# CPU_CORE_POWER_GND.net
KiCad netlist of a schematic drawn in Altium Designer
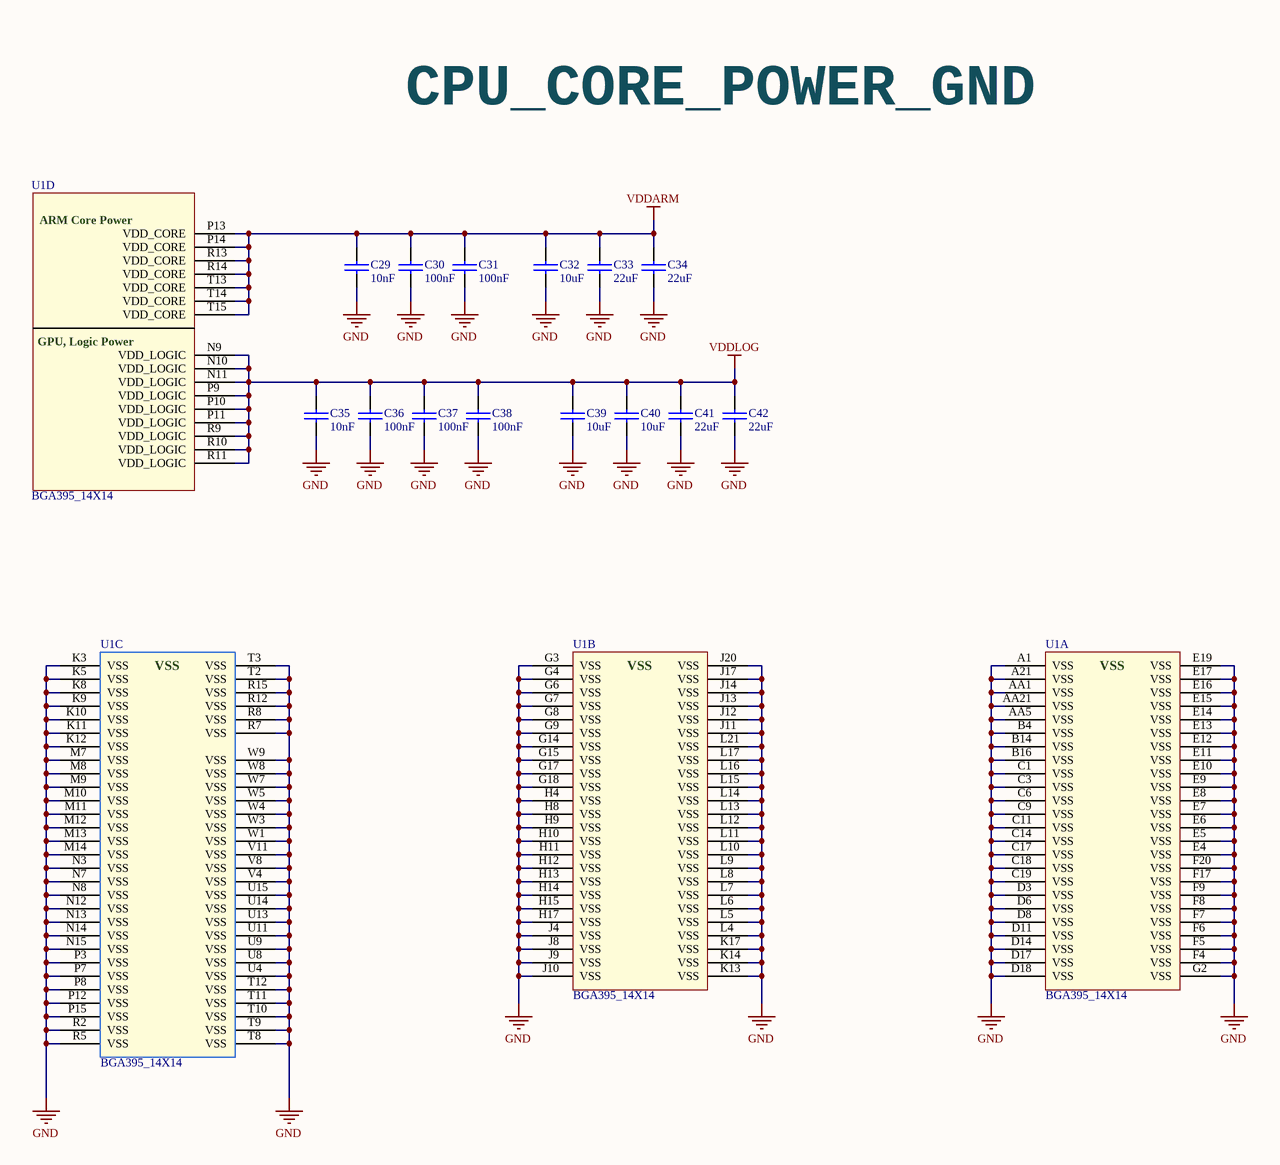
[diagram p0: CPU_CORE_POWER_GND.SchDoc]

(export (version "E")
  (design (tool "Eeschema 10.0.6"))
  (components
    (comp (ref "C29")
      (value "10nF")
      (footprint "0402_CC - C")
      (libsource (lib "AAR_RockChip_RK3328") (part "CAP_NP"))
    )
    (comp (ref "C30")
      (value "100nF")
      (footprint "0402_CC - C")
      (libsource (lib "AAR_RockChip_RK3328") (part "CAP_NP"))
    )
    (comp (ref "C31")
      (value "100nF")
      (footprint "0402_CC - C")
      (libsource (lib "AAR_RockChip_RK3328") (part "CAP_NP"))
    )
    (comp (ref "C32")
      (value "10uF")
      (footprint "0603_CC")
      (libsource (lib "AAR_RockChip_RK3328") (part "CAP_NP"))
    )
    (comp (ref "C33")
      (value "22uF")
      (footprint "0603_CC")
      (libsource (lib "AAR_RockChip_RK3328") (part "CAP_NP"))
    )
    (comp (ref "C34")
      (value "22uF")
      (footprint "0603_CC")
      (libsource (lib "AAR_RockChip_RK3328") (part "CAP_NP"))
    )
    (comp (ref "C35")
      (value "10nF")
      (footprint "0402_CC - C")
      (libsource (lib "AAR_RockChip_RK3328") (part "CAP_NP"))
    )
    (comp (ref "C36")
      (value "100nF")
      (footprint "0402_CC - C")
      (libsource (lib "AAR_RockChip_RK3328") (part "CAP_NP"))
    )
    (comp (ref "C37")
      (value "100nF")
      (footprint "0402_CC - C")
      (libsource (lib "AAR_RockChip_RK3328") (part "CAP_NP"))
    )
    (comp (ref "C38")
      (value "100nF")
      (footprint "0402_CC - C")
      (libsource (lib "AAR_RockChip_RK3328") (part "CAP_NP"))
    )
    (comp (ref "C39")
      (value "10uF")
      (footprint "0603_CC")
      (libsource (lib "AAR_RockChip_RK3328") (part "CAP_NP"))
    )
    (comp (ref "C40")
      (value "10uF")
      (footprint "0603_CC")
      (libsource (lib "AAR_RockChip_RK3328") (part "CAP_NP"))
    )
    (comp (ref "C41")
      (value "22uF")
      (footprint "0603_CC")
      (libsource (lib "AAR_RockChip_RK3328") (part "CAP_NP"))
    )
    (comp (ref "C42")
      (value "22uF")
      (footprint "0603_CC")
      (libsource (lib "AAR_RockChip_RK3328") (part "CAP_NP"))
    )
    (comp (ref "U1")
      (value "BGA395_14X14")
      (footprint "BGA395C65P21X21_1750X1750X117")
      (description "By AAR")
      (libsource (lib "AAR_RockChip_RK3328") (part "RK3328"))
    )
  )
  (nets
    (net (code "1") (name "GND") (class "Default")
      (node (ref "C29") (pin "2") (pinfunction "2_2") (pintype "passive"))
      (node (ref "C30") (pin "2") (pinfunction "2_2") (pintype "passive"))
      (node (ref "C31") (pin "2") (pinfunction "2_2") (pintype "passive"))
      (node (ref "C32") (pin "2") (pinfunction "2_2") (pintype "passive"))
      (node (ref "C33") (pin "2") (pinfunction "2_2") (pintype "passive"))
      (node (ref "C34") (pin "2") (pinfunction "2_2") (pintype "passive"))
      (node (ref "C35") (pin "2") (pinfunction "2_2") (pintype "passive"))
      (node (ref "C36") (pin "2") (pinfunction "2_2") (pintype "passive"))
      (node (ref "C37") (pin "2") (pinfunction "2_2") (pintype "passive"))
      (node (ref "C38") (pin "2") (pinfunction "2_2") (pintype "passive"))
      (node (ref "C39") (pin "2") (pinfunction "2_2") (pintype "passive"))
      (node (ref "C40") (pin "2") (pinfunction "2_2") (pintype "passive"))
      (node (ref "C41") (pin "2") (pinfunction "2_2") (pintype "passive"))
      (node (ref "C42") (pin "2") (pinfunction "2_2") (pintype "passive"))
      (node (ref "U1") (pin "A1") (pinfunction "VSS_A1") (pintype "power_in"))
      (node (ref "U1") (pin "A21") (pinfunction "VSS_A21") (pintype "power_in"))
      (node (ref "U1") (pin "AA1") (pinfunction "VSS_AA1") (pintype "power_in"))
      (node (ref "U1") (pin "AA21") (pinfunction "VSS_AA21") (pintype "power_in"))
      (node (ref "U1") (pin "AA5") (pinfunction "VSS_AA5") (pintype "power_in"))
      (node (ref "U1") (pin "B14") (pinfunction "VSS_B14") (pintype "power_in"))
      (node (ref "U1") (pin "B16") (pinfunction "VSS_B16") (pintype "power_in"))
      (node (ref "U1") (pin "B4") (pinfunction "VSS_B4") (pintype "power_in"))
      (node (ref "U1") (pin "C1") (pinfunction "VSS_C1") (pintype "power_in"))
      (node (ref "U1") (pin "C11") (pinfunction "VSS_C11") (pintype "power_in"))
      (node (ref "U1") (pin "C14") (pinfunction "VSS_C14") (pintype "power_in"))
      (node (ref "U1") (pin "C17") (pinfunction "VSS_C17") (pintype "power_in"))
      (node (ref "U1") (pin "C18") (pinfunction "VSS_C18") (pintype "power_in"))
      (node (ref "U1") (pin "C19") (pinfunction "VSS_C19") (pintype "power_in"))
      (node (ref "U1") (pin "C3") (pinfunction "VSS_C3") (pintype "power_in"))
      (node (ref "U1") (pin "C6") (pinfunction "VSS_C6") (pintype "power_in"))
      (node (ref "U1") (pin "C9") (pinfunction "VSS_C9") (pintype "power_in"))
      (node (ref "U1") (pin "D11") (pinfunction "VSS_D11") (pintype "power_in"))
      (node (ref "U1") (pin "D14") (pinfunction "VSS_D14") (pintype "power_in"))
      (node (ref "U1") (pin "D17") (pinfunction "VSS_D17") (pintype "power_in"))
      (node (ref "U1") (pin "D18") (pinfunction "VSS_D18") (pintype "power_in"))
      (node (ref "U1") (pin "D3") (pinfunction "VSS_D3") (pintype "power_in"))
      (node (ref "U1") (pin "D6") (pinfunction "VSS_D6") (pintype "power_in"))
      (node (ref "U1") (pin "D8") (pinfunction "VSS_D8") (pintype "power_in"))
      (node (ref "U1") (pin "E10") (pinfunction "VSS_E10") (pintype "power_in"))
      (node (ref "U1") (pin "E11") (pinfunction "VSS_E11") (pintype "power_in"))
      (node (ref "U1") (pin "E12") (pinfunction "VSS_E12") (pintype "power_in"))
      (node (ref "U1") (pin "E13") (pinfunction "VSS_E13") (pintype "power_in"))
      (node (ref "U1") (pin "E14") (pinfunction "VSS_E14") (pintype "power_in"))
      (node (ref "U1") (pin "E15") (pinfunction "VSS_E15") (pintype "power_in"))
      (node (ref "U1") (pin "E16") (pinfunction "VSS_E16") (pintype "power_in"))
      (node (ref "U1") (pin "E17") (pinfunction "VSS_E17") (pintype "power_in"))
      (node (ref "U1") (pin "E19") (pinfunction "VSS_E19") (pintype "power_in"))
      (node (ref "U1") (pin "E4") (pinfunction "VSS_E4") (pintype "power_in"))
      (node (ref "U1") (pin "E5") (pinfunction "VSS_E5") (pintype "power_in"))
      (node (ref "U1") (pin "E6") (pinfunction "VSS_E6") (pintype "power_in"))
      (node (ref "U1") (pin "E7") (pinfunction "VSS_E7") (pintype "power_in"))
      (node (ref "U1") (pin "E8") (pinfunction "VSS_E8") (pintype "power_in"))
      (node (ref "U1") (pin "E9") (pinfunction "VSS_E9") (pintype "power_in"))
      (node (ref "U1") (pin "F17") (pinfunction "VSS_F17") (pintype "power_in"))
      (node (ref "U1") (pin "F20") (pinfunction "VSS_F20") (pintype "power_in"))
      (node (ref "U1") (pin "F4") (pinfunction "VSS_F4") (pintype "power_in"))
      (node (ref "U1") (pin "F5") (pinfunction "VSS_F5") (pintype "power_in"))
      (node (ref "U1") (pin "F6") (pinfunction "VSS_F6") (pintype "power_in"))
      (node (ref "U1") (pin "F7") (pinfunction "VSS_F7") (pintype "power_in"))
      (node (ref "U1") (pin "F8") (pinfunction "VSS_F8") (pintype "power_in"))
      (node (ref "U1") (pin "F9") (pinfunction "VSS_F9") (pintype "power_in"))
      (node (ref "U1") (pin "G14") (pinfunction "VSS_G14") (pintype "power_in"))
      (node (ref "U1") (pin "G15") (pinfunction "VSS_G15") (pintype "power_in"))
      (node (ref "U1") (pin "G17") (pinfunction "VSS_G17") (pintype "power_in"))
      (node (ref "U1") (pin "G18") (pinfunction "VSS_G18") (pintype "power_in"))
      (node (ref "U1") (pin "G2") (pinfunction "VSS_G2") (pintype "power_in"))
      (node (ref "U1") (pin "G3") (pinfunction "VSS_G3") (pintype "power_in"))
      (node (ref "U1") (pin "G4") (pinfunction "VSS_G4") (pintype "power_in"))
      (node (ref "U1") (pin "G6") (pinfunction "VSS_G6") (pintype "power_in"))
      (node (ref "U1") (pin "G7") (pinfunction "VSS_G7") (pintype "power_in"))
      (node (ref "U1") (pin "G8") (pinfunction "VSS_G8") (pintype "power_in"))
      (node (ref "U1") (pin "G9") (pinfunction "VSS_G9") (pintype "power_in"))
      (node (ref "U1") (pin "H10") (pinfunction "VSS_H10") (pintype "power_in"))
      (node (ref "U1") (pin "H11") (pinfunction "VSS_H11") (pintype "power_in"))
      (node (ref "U1") (pin "H12") (pinfunction "VSS_H12") (pintype "power_in"))
      (node (ref "U1") (pin "H13") (pinfunction "VSS_H13") (pintype "power_in"))
      (node (ref "U1") (pin "H14") (pinfunction "VSS_H14") (pintype "power_in"))
      (node (ref "U1") (pin "H15") (pinfunction "VSS_H15") (pintype "power_in"))
      (node (ref "U1") (pin "H17") (pinfunction "VSS_H17") (pintype "power_in"))
      (node (ref "U1") (pin "H4") (pinfunction "VSS_H4") (pintype "power_in"))
      (node (ref "U1") (pin "H8") (pinfunction "VSS_H8") (pintype "power_in"))
      (node (ref "U1") (pin "H9") (pinfunction "VSS_H9") (pintype "power_in"))
      (node (ref "U1") (pin "J10") (pinfunction "VSS_J10") (pintype "power_in"))
      (node (ref "U1") (pin "J11") (pinfunction "VSS_J11") (pintype "power_in"))
      (node (ref "U1") (pin "J12") (pinfunction "VSS_J12") (pintype "power_in"))
      (node (ref "U1") (pin "J13") (pinfunction "VSS_J13") (pintype "power_in"))
      (node (ref "U1") (pin "J14") (pinfunction "VSS_J14") (pintype "power_in"))
      (node (ref "U1") (pin "J17") (pinfunction "VSS_J17") (pintype "power_in"))
      (node (ref "U1") (pin "J20") (pinfunction "VSS_J20") (pintype "power_in"))
      (node (ref "U1") (pin "J4") (pinfunction "VSS_J4") (pintype "power_in"))
      (node (ref "U1") (pin "J8") (pinfunction "VSS_J8") (pintype "power_in"))
      (node (ref "U1") (pin "J9") (pinfunction "VSS_J9") (pintype "power_in"))
      (node (ref "U1") (pin "K10") (pinfunction "VSS_K10") (pintype "power_in"))
      (node (ref "U1") (pin "K11") (pinfunction "VSS_K11") (pintype "power_in"))
      (node (ref "U1") (pin "K12") (pinfunction "VSS_K12") (pintype "power_in"))
      (node (ref "U1") (pin "K13") (pinfunction "VSS_K13") (pintype "power_in"))
      (node (ref "U1") (pin "K14") (pinfunction "VSS_K14") (pintype "power_in"))
      (node (ref "U1") (pin "K17") (pinfunction "VSS_K17") (pintype "power_in"))
      (node (ref "U1") (pin "K3") (pinfunction "VSS_K3") (pintype "power_in"))
      (node (ref "U1") (pin "K5") (pinfunction "VSS_K5") (pintype "power_in"))
      (node (ref "U1") (pin "K8") (pinfunction "VSS_K8") (pintype "power_in"))
      (node (ref "U1") (pin "K9") (pinfunction "VSS_K9") (pintype "power_in"))
      (node (ref "U1") (pin "L10") (pinfunction "VSS_L10") (pintype "power_in"))
      (node (ref "U1") (pin "L11") (pinfunction "VSS_L11") (pintype "power_in"))
      (node (ref "U1") (pin "L12") (pinfunction "VSS_L12") (pintype "power_in"))
      (node (ref "U1") (pin "L13") (pinfunction "VSS_L13") (pintype "power_in"))
      (node (ref "U1") (pin "L14") (pinfunction "VSS_L14") (pintype "power_in"))
      (node (ref "U1") (pin "L15") (pinfunction "VSS_L15") (pintype "power_in"))
      (node (ref "U1") (pin "L16") (pinfunction "VSS_L16") (pintype "power_in"))
      (node (ref "U1") (pin "L17") (pinfunction "VSS_L17") (pintype "power_in"))
      (node (ref "U1") (pin "L21") (pinfunction "VSS_L21") (pintype "power_in"))
      (node (ref "U1") (pin "L4") (pinfunction "VSS_L4") (pintype "power_in"))
      (node (ref "U1") (pin "L5") (pinfunction "VSS_L5") (pintype "power_in"))
      (node (ref "U1") (pin "L6") (pinfunction "VSS_L6") (pintype "power_in"))
      (node (ref "U1") (pin "L7") (pinfunction "VSS_L7") (pintype "power_in"))
      (node (ref "U1") (pin "L8") (pinfunction "VSS_L8") (pintype "power_in"))
      (node (ref "U1") (pin "L9") (pinfunction "VSS_L9") (pintype "power_in"))
      (node (ref "U1") (pin "M10") (pinfunction "VSS_M10") (pintype "power_in"))
      (node (ref "U1") (pin "M11") (pinfunction "VSS_M11") (pintype "power_in"))
      (node (ref "U1") (pin "M12") (pinfunction "VSS_M12") (pintype "power_in"))
      (node (ref "U1") (pin "M13") (pinfunction "VSS_M13") (pintype "power_in"))
      (node (ref "U1") (pin "M14") (pinfunction "VSS_M14") (pintype "power_in"))
      (node (ref "U1") (pin "M7") (pinfunction "VSS_M7") (pintype "power_in"))
      (node (ref "U1") (pin "M8") (pinfunction "VSS_M8") (pintype "power_in"))
      (node (ref "U1") (pin "M9") (pinfunction "VSS_M9") (pintype "power_in"))
      (node (ref "U1") (pin "N12") (pinfunction "VSS_N12") (pintype "power_in"))
      (node (ref "U1") (pin "N13") (pinfunction "VSS_N13") (pintype "power_in"))
      (node (ref "U1") (pin "N14") (pinfunction "VSS_N14") (pintype "power_in"))
      (node (ref "U1") (pin "N15") (pinfunction "VSS_N15") (pintype "power_in"))
      (node (ref "U1") (pin "N3") (pinfunction "VSS_N3") (pintype "power_in"))
      (node (ref "U1") (pin "N7") (pinfunction "VSS_N7") (pintype "power_in"))
      (node (ref "U1") (pin "N8") (pinfunction "VSS_N8") (pintype "power_in"))
      (node (ref "U1") (pin "P12") (pinfunction "VSS_P12") (pintype "power_in"))
      (node (ref "U1") (pin "P15") (pinfunction "VSS_P15") (pintype "power_in"))
      (node (ref "U1") (pin "P3") (pinfunction "VSS_P3") (pintype "power_in"))
      (node (ref "U1") (pin "P7") (pinfunction "VSS_P7") (pintype "power_in"))
      (node (ref "U1") (pin "P8") (pinfunction "VSS_P8") (pintype "power_in"))
      (node (ref "U1") (pin "R12") (pinfunction "VSS_R12") (pintype "power_in"))
      (node (ref "U1") (pin "R15") (pinfunction "VSS_R15") (pintype "power_in"))
      (node (ref "U1") (pin "R2") (pinfunction "VSS_R2") (pintype "power_in"))
      (node (ref "U1") (pin "R5") (pinfunction "VSS_R5") (pintype "power_in"))
      (node (ref "U1") (pin "R7") (pinfunction "VSS_R7") (pintype "power_in"))
      (node (ref "U1") (pin "R8") (pinfunction "VSS_R8") (pintype "power_in"))
      (node (ref "U1") (pin "T10") (pinfunction "VSS_T10") (pintype "power_in"))
      (node (ref "U1") (pin "T11") (pinfunction "VSS_T11") (pintype "power_in"))
      (node (ref "U1") (pin "T12") (pinfunction "VSS_T12") (pintype "power_in"))
      (node (ref "U1") (pin "T2") (pinfunction "VSS_T2") (pintype "power_in"))
      (node (ref "U1") (pin "T3") (pinfunction "VSS_T3") (pintype "power_in"))
      (node (ref "U1") (pin "T8") (pinfunction "VSS_T8") (pintype "power_in"))
      (node (ref "U1") (pin "T9") (pinfunction "VSS_T9") (pintype "power_in"))
      (node (ref "U1") (pin "U11") (pinfunction "VSS_U11") (pintype "power_in"))
      (node (ref "U1") (pin "U13") (pinfunction "VSS_U13") (pintype "power_in"))
      (node (ref "U1") (pin "U14") (pinfunction "VSS_U14") (pintype "power_in"))
      (node (ref "U1") (pin "U15") (pinfunction "VSS_U15") (pintype "power_in"))
      (node (ref "U1") (pin "U4") (pinfunction "VSS_U4") (pintype "power_in"))
      (node (ref "U1") (pin "U8") (pinfunction "VSS_U8") (pintype "power_in"))
      (node (ref "U1") (pin "U9") (pinfunction "VSS_U9") (pintype "power_in"))
      (node (ref "U1") (pin "V11") (pinfunction "VSS_V11") (pintype "power_in"))
      (node (ref "U1") (pin "V4") (pinfunction "VSS_V4") (pintype "power_in"))
      (node (ref "U1") (pin "V8") (pinfunction "VSS_V8") (pintype "power_in"))
      (node (ref "U1") (pin "W1") (pinfunction "VSS_W1") (pintype "power_in"))
      (node (ref "U1") (pin "W3") (pinfunction "VSS_W3") (pintype "power_in"))
      (node (ref "U1") (pin "W4") (pinfunction "VSS_W4") (pintype "power_in"))
      (node (ref "U1") (pin "W5") (pinfunction "VSS_W5") (pintype "power_in"))
      (node (ref "U1") (pin "W7") (pinfunction "VSS_W7") (pintype "power_in"))
      (node (ref "U1") (pin "W8") (pinfunction "VSS_W8") (pintype "power_in"))
      (node (ref "U1") (pin "W9") (pinfunction "VSS_W9") (pintype "power_in"))
    )
    (net (code "2") (name "VDDARM") (class "Default")
      (node (ref "C29") (pin "1") (pinfunction "1_1") (pintype "passive"))
      (node (ref "C30") (pin "1") (pinfunction "1_1") (pintype "passive"))
      (node (ref "C31") (pin "1") (pinfunction "1_1") (pintype "passive"))
      (node (ref "C32") (pin "1") (pinfunction "1_1") (pintype "passive"))
      (node (ref "C33") (pin "1") (pinfunction "1_1") (pintype "passive"))
      (node (ref "C34") (pin "1") (pinfunction "1_1") (pintype "passive"))
      (node (ref "U1") (pin "P13") (pinfunction "VDD_CORE_P13") (pintype "power_in"))
      (node (ref "U1") (pin "P14") (pinfunction "VDD_CORE_P14") (pintype "power_in"))
      (node (ref "U1") (pin "R13") (pinfunction "VDD_CORE_R13") (pintype "power_in"))
      (node (ref "U1") (pin "R14") (pinfunction "VDD_CORE_R14") (pintype "power_in"))
      (node (ref "U1") (pin "T13") (pinfunction "VDD_CORE_T13") (pintype "power_in"))
      (node (ref "U1") (pin "T14") (pinfunction "VDD_CORE_T14") (pintype "power_in"))
      (node (ref "U1") (pin "T15") (pinfunction "VDD_CORE_T15") (pintype "power_in"))
    )
    (net (code "3") (name "VDDLOG") (class "Default")
      (node (ref "C35") (pin "1") (pinfunction "1_1") (pintype "passive"))
      (node (ref "C36") (pin "1") (pinfunction "1_1") (pintype "passive"))
      (node (ref "C37") (pin "1") (pinfunction "1_1") (pintype "passive"))
      (node (ref "C38") (pin "1") (pinfunction "1_1") (pintype "passive"))
      (node (ref "C39") (pin "1") (pinfunction "1_1") (pintype "passive"))
      (node (ref "C40") (pin "1") (pinfunction "1_1") (pintype "passive"))
      (node (ref "C41") (pin "1") (pinfunction "1_1") (pintype "passive"))
      (node (ref "C42") (pin "1") (pinfunction "1_1") (pintype "passive"))
      (node (ref "U1") (pin "N10") (pinfunction "VDD_LOGIC_N10") (pintype "power_in"))
      (node (ref "U1") (pin "N11") (pinfunction "VDD_LOGIC_N11") (pintype "power_in"))
      (node (ref "U1") (pin "N9") (pinfunction "VDD_LOGIC_N9") (pintype "power_in"))
      (node (ref "U1") (pin "P10") (pinfunction "VDD_LOGIC_P10") (pintype "power_in"))
      (node (ref "U1") (pin "P11") (pinfunction "VDD_LOGIC_P11") (pintype "power_in"))
      (node (ref "U1") (pin "P9") (pinfunction "VDD_LOGIC_P9") (pintype "power_in"))
      (node (ref "U1") (pin "R10") (pinfunction "VDD_LOGIC_R10") (pintype "power_in"))
      (node (ref "U1") (pin "R11") (pinfunction "VDD_LOGIC_R11") (pintype "power_in"))
      (node (ref "U1") (pin "R9") (pinfunction "VDD_LOGIC_R9") (pintype "power_in"))
    )
  )
)
